# pcb.net
KiCad netlist of a schematic drawn in EAGLE
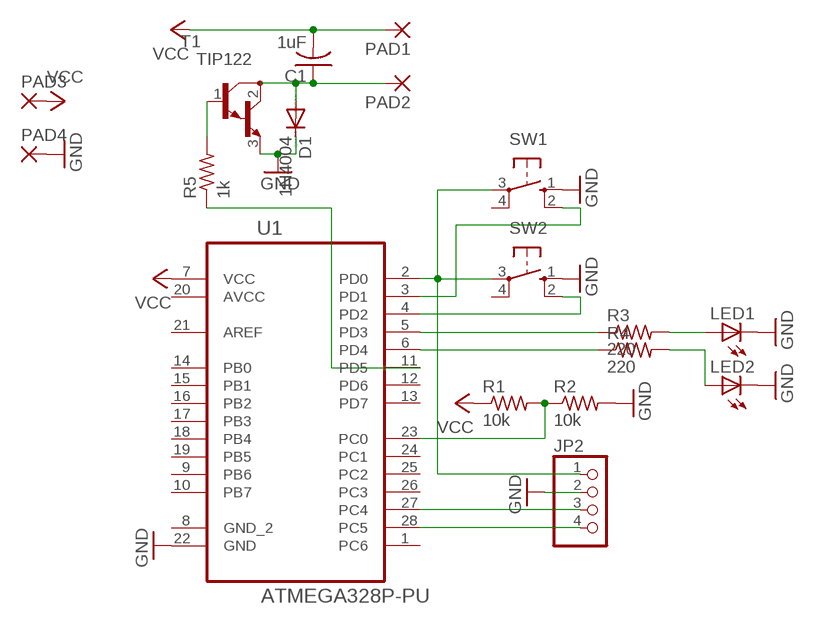
[diagram p0: schematic, sheet 1]

(export (version "E")
  (design (tool "Eeschema 10.0.6"))
  (components
    (comp (ref "C1")
      (value "1uF")
      (footprint "eagle-import:C025-025X050")
      (libsource (lib "eagle-import") (part "C-US025-025X050"))
    )
    (comp (ref "D1")
      (value "1N4004")
      (footprint "eagle-import:DO41-10")
      (libsource (lib "eagle-import") (part "1N4004"))
    )
    (comp (ref "JP2")
      (value "PINHD-1X4")
      (footprint "eagle-import:1X04")
      (libsource (lib "eagle-import") (part "PINHD-1X4"))
    )
    (comp (ref "LED1")
      (value "LED5MM")
      (footprint "eagle-import:LED5MM")
      (libsource (lib "eagle-import") (part "LED5MM"))
    )
    (comp (ref "LED2")
      (value "LED5MM")
      (footprint "eagle-import:LED5MM")
      (libsource (lib "eagle-import") (part "LED5MM"))
    )
    (comp (ref "PAD1")
      (value "1,6/0,8")
      (footprint "eagle-import:1,6_0,8")
      (libsource (lib "eagle-import") (part "1,6/0,8"))
    )
    (comp (ref "PAD2")
      (value "1,6/0,8")
      (footprint "eagle-import:1,6_0,8")
      (libsource (lib "eagle-import") (part "1,6/0,8"))
    )
    (comp (ref "PAD3")
      (value "1,6/0,8")
      (footprint "eagle-import:1,6_0,8")
      (libsource (lib "eagle-import") (part "1,6/0,8"))
    )
    (comp (ref "PAD4")
      (value "1,6/0,8")
      (footprint "eagle-import:1,6_0,8")
      (libsource (lib "eagle-import") (part "1,6/0,8"))
    )
    (comp (ref "R1")
      (value "10k")
      (footprint "eagle-import:0204_5")
      (libsource (lib "eagle-import") (part "R-US_0204/5"))
    )
    (comp (ref "R2")
      (value "10k")
      (footprint "eagle-import:0204_5")
      (libsource (lib "eagle-import") (part "R-US_0204/5"))
    )
    (comp (ref "R3")
      (value "220")
      (footprint "eagle-import:0204_5")
      (libsource (lib "eagle-import") (part "R-US_0204/5"))
    )
    (comp (ref "R4")
      (value "220")
      (footprint "eagle-import:0204_5")
      (libsource (lib "eagle-import") (part "R-US_0204/5"))
    )
    (comp (ref "R5")
      (value "1k")
      (footprint "eagle-import:0204_5")
      (libsource (lib "eagle-import") (part "R-US_0204/5"))
    )
    (comp (ref "SW1")
      (value "10-XX")
      (footprint "eagle-import:B3F-10XX")
      (libsource (lib "eagle-import") (part "10-XX"))
    )
    (comp (ref "SW2")
      (value "10-XX")
      (footprint "eagle-import:B3F-10XX")
      (libsource (lib "eagle-import") (part "10-XX"))
    )
    (comp (ref "T1")
      (value "TIP122")
      (footprint "eagle-import:TO220")
      (libsource (lib "eagle-import") (part "TIP122"))
    )
    (comp (ref "U1")
      (value "ATMEGA328P-PU")
      (footprint "eagle-import:DIP254P762X457-28")
      (libsource (lib "eagle-import") (part "ATMEGA328P-PU"))
    )
  )
  (nets
    (net (code "1") (name "/AVCC") (class "Default")
      (node (ref "U1") (pin "20") (pinfunction "AVCC_20") (pintype "power_in"))
    )
    (net (code "2") (name "GND") (class "Default")
      (node (ref "D1") (pin "C") (pinfunction "C_C") (pintype "passive"))
      (node (ref "JP2") (pin "2") (pinfunction "2_2") (pintype "passive"))
      (node (ref "LED1") (pin "K") (pinfunction "C_K") (pintype "passive"))
      (node (ref "LED2") (pin "K") (pinfunction "C_K") (pintype "passive"))
      (node (ref "PAD4") (pin "1") (pinfunction "P_1") (pintype "passive"))
      (node (ref "R2") (pin "2") (pinfunction "2_2") (pintype "passive"))
      (node (ref "SW1") (pin "1") (pinfunction "S_1") (pintype "passive"))
      (node (ref "SW2") (pin "1") (pinfunction "S_1") (pintype "passive"))
      (node (ref "T1") (pin "3") (pinfunction "E_3") (pintype "passive"))
      (node (ref "U1") (pin "22") (pinfunction "GND_22") (pintype "passive"))
    )
    (net (code "3") (name "Net-(LED1-PadA)") (class "Default")
      (node (ref "LED1") (pin "A") (pinfunction "A_A") (pintype "passive"))
      (node (ref "R3") (pin "2") (pinfunction "2_2") (pintype "passive"))
    )
    (net (code "4") (name "Net-(LED2-PadA)") (class "Default")
      (node (ref "LED2") (pin "A") (pinfunction "A_A") (pintype "passive"))
      (node (ref "R4") (pin "2") (pinfunction "2_2") (pintype "passive"))
    )
    (net (code "5") (name "Net-(PAD2-P)") (class "Default")
      (node (ref "C1") (pin "1") (pinfunction "1_1") (pintype "passive"))
      (node (ref "D1") (pin "A") (pinfunction "A_A") (pintype "passive"))
      (node (ref "PAD2") (pin "1") (pinfunction "P_1") (pintype "passive"))
      (node (ref "T1") (pin "2") (pinfunction "C_2") (pintype "passive"))
    )
    (net (code "6") (name "Net-(SW1-P)") (class "Default")
      (node (ref "JP2") (pin "1") (pinfunction "1_1") (pintype "passive"))
      (node (ref "SW1") (pin "3") (pinfunction "P_3") (pintype "passive"))
      (node (ref "SW2") (pin "3") (pinfunction "P_3") (pintype "passive"))
      (node (ref "U1") (pin "2") (pinfunction "PD0_2") (pintype "bidirectional"))
    )
    (net (code "7") (name "Net-(SW1-S1)") (class "Default")
      (node (ref "SW1") (pin "2") (pinfunction "S1_2") (pintype "passive"))
      (node (ref "U1") (pin "3") (pinfunction "PD1_3") (pintype "bidirectional"))
    )
    (net (code "8") (name "Net-(SW2-S1)") (class "Default")
      (node (ref "SW2") (pin "2") (pinfunction "S1_2") (pintype "passive"))
      (node (ref "U1") (pin "4") (pinfunction "PD2_4") (pintype "bidirectional"))
    )
    (net (code "9") (name "Net-(T1-B)") (class "Default")
      (node (ref "R5") (pin "2") (pinfunction "2_2") (pintype "passive"))
      (node (ref "T1") (pin "1") (pinfunction "B_1") (pintype "passive"))
    )
    (net (code "10") (name "Net-(U1-PC0)") (class "Default")
      (node (ref "R1") (pin "2") (pinfunction "2_2") (pintype "passive"))
      (node (ref "R2") (pin "1") (pinfunction "1_1") (pintype "passive"))
      (node (ref "U1") (pin "23") (pinfunction "PC0_23") (pintype "bidirectional"))
    )
    (net (code "11") (name "Net-(U1-PC4)") (class "Default")
      (node (ref "JP2") (pin "3") (pinfunction "3_3") (pintype "passive"))
      (node (ref "U1") (pin "27") (pinfunction "PC4_27") (pintype "bidirectional"))
    )
    (net (code "12") (name "Net-(U1-PC5)") (class "Default")
      (node (ref "JP2") (pin "4") (pinfunction "4_4") (pintype "passive"))
      (node (ref "U1") (pin "28") (pinfunction "PC5_28") (pintype "bidirectional"))
    )
    (net (code "13") (name "Net-(U1-PD3)") (class "Default")
      (node (ref "R3") (pin "1") (pinfunction "1_1") (pintype "passive"))
      (node (ref "U1") (pin "5") (pinfunction "PD3_5") (pintype "bidirectional"))
    )
    (net (code "14") (name "Net-(U1-PD4)") (class "Default")
      (node (ref "R4") (pin "1") (pinfunction "1_1") (pintype "passive"))
      (node (ref "U1") (pin "6") (pinfunction "PD4_6") (pintype "bidirectional"))
    )
    (net (code "15") (name "Net-(U1-PD5)") (class "Default")
      (node (ref "R5") (pin "1") (pinfunction "1_1") (pintype "passive"))
      (node (ref "U1") (pin "11") (pinfunction "PD5_11") (pintype "bidirectional"))
    )
    (net (code "16") (name "VCC") (class "Default")
      (node (ref "C1") (pin "2") (pinfunction "2_2") (pintype "passive"))
      (node (ref "PAD1") (pin "1") (pinfunction "P_1") (pintype "passive"))
      (node (ref "PAD3") (pin "1") (pinfunction "P_1") (pintype "passive"))
      (node (ref "R1") (pin "1") (pinfunction "1_1") (pintype "passive"))
      (node (ref "U1") (pin "7") (pinfunction "VCC_7") (pintype "power_in"))
    )
    (net (code "17") (name "unconnected-(SW1-P1-Pad4)") (class "Default")
      (node (ref "SW1") (pin "4") (pinfunction "P1_4") (pintype "passive"))
    )
    (net (code "18") (name "unconnected-(SW2-P1-Pad4)") (class "Default")
      (node (ref "SW2") (pin "4") (pinfunction "P1_4") (pintype "passive"))
    )
    (net (code "19") (name "unconnected-(U1-AREF-Pad21)") (class "Default")
      (node (ref "U1") (pin "21") (pinfunction "AREF_21") (pintype "input"))
    )
    (net (code "20") (name "unconnected-(U1-GND_2-Pad8)") (class "Default")
      (node (ref "U1") (pin "8") (pinfunction "GND_2_8") (pintype "passive"))
    )
    (net (code "21") (name "unconnected-(U1-PB0-Pad14)") (class "Default")
      (node (ref "U1") (pin "14") (pinfunction "PB0_14") (pintype "bidirectional"))
    )
    (net (code "22") (name "unconnected-(U1-PB1-Pad15)") (class "Default")
      (node (ref "U1") (pin "15") (pinfunction "PB1_15") (pintype "bidirectional"))
    )
    (net (code "23") (name "unconnected-(U1-PB2-Pad16)") (class "Default")
      (node (ref "U1") (pin "16") (pinfunction "PB2_16") (pintype "bidirectional"))
    )
    (net (code "24") (name "unconnected-(U1-PB3-Pad17)") (class "Default")
      (node (ref "U1") (pin "17") (pinfunction "PB3_17") (pintype "bidirectional"))
    )
    (net (code "25") (name "unconnected-(U1-PB4-Pad18)") (class "Default")
      (node (ref "U1") (pin "18") (pinfunction "PB4_18") (pintype "bidirectional"))
    )
    (net (code "26") (name "unconnected-(U1-PB5-Pad19)") (class "Default")
      (node (ref "U1") (pin "19") (pinfunction "PB5_19") (pintype "bidirectional"))
    )
    (net (code "27") (name "unconnected-(U1-PB6-Pad9)") (class "Default")
      (node (ref "U1") (pin "9") (pinfunction "PB6_9") (pintype "bidirectional"))
    )
    (net (code "28") (name "unconnected-(U1-PB7-Pad10)") (class "Default")
      (node (ref "U1") (pin "10") (pinfunction "PB7_10") (pintype "bidirectional"))
    )
    (net (code "29") (name "unconnected-(U1-PC1-Pad24)") (class "Default")
      (node (ref "U1") (pin "24") (pinfunction "PC1_24") (pintype "bidirectional"))
    )
    (net (code "30") (name "unconnected-(U1-PC2-Pad25)") (class "Default")
      (node (ref "U1") (pin "25") (pinfunction "PC2_25") (pintype "bidirectional"))
    )
    (net (code "31") (name "unconnected-(U1-PC3-Pad26)") (class "Default")
      (node (ref "U1") (pin "26") (pinfunction "PC3_26") (pintype "bidirectional"))
    )
    (net (code "32") (name "unconnected-(U1-PC6-Pad1)") (class "Default")
      (node (ref "U1") (pin "1") (pinfunction "PC6_1") (pintype "bidirectional"))
    )
    (net (code "33") (name "unconnected-(U1-PD6-Pad12)") (class "Default")
      (node (ref "U1") (pin "12") (pinfunction "PD6_12") (pintype "bidirectional"))
    )
    (net (code "34") (name "unconnected-(U1-PD7-Pad13)") (class "Default")
      (node (ref "U1") (pin "13") (pinfunction "PD7_13") (pintype "bidirectional"))
    )
  )
)
